# DAC.net
KiCad netlist of a schematic drawn in Altium Designer
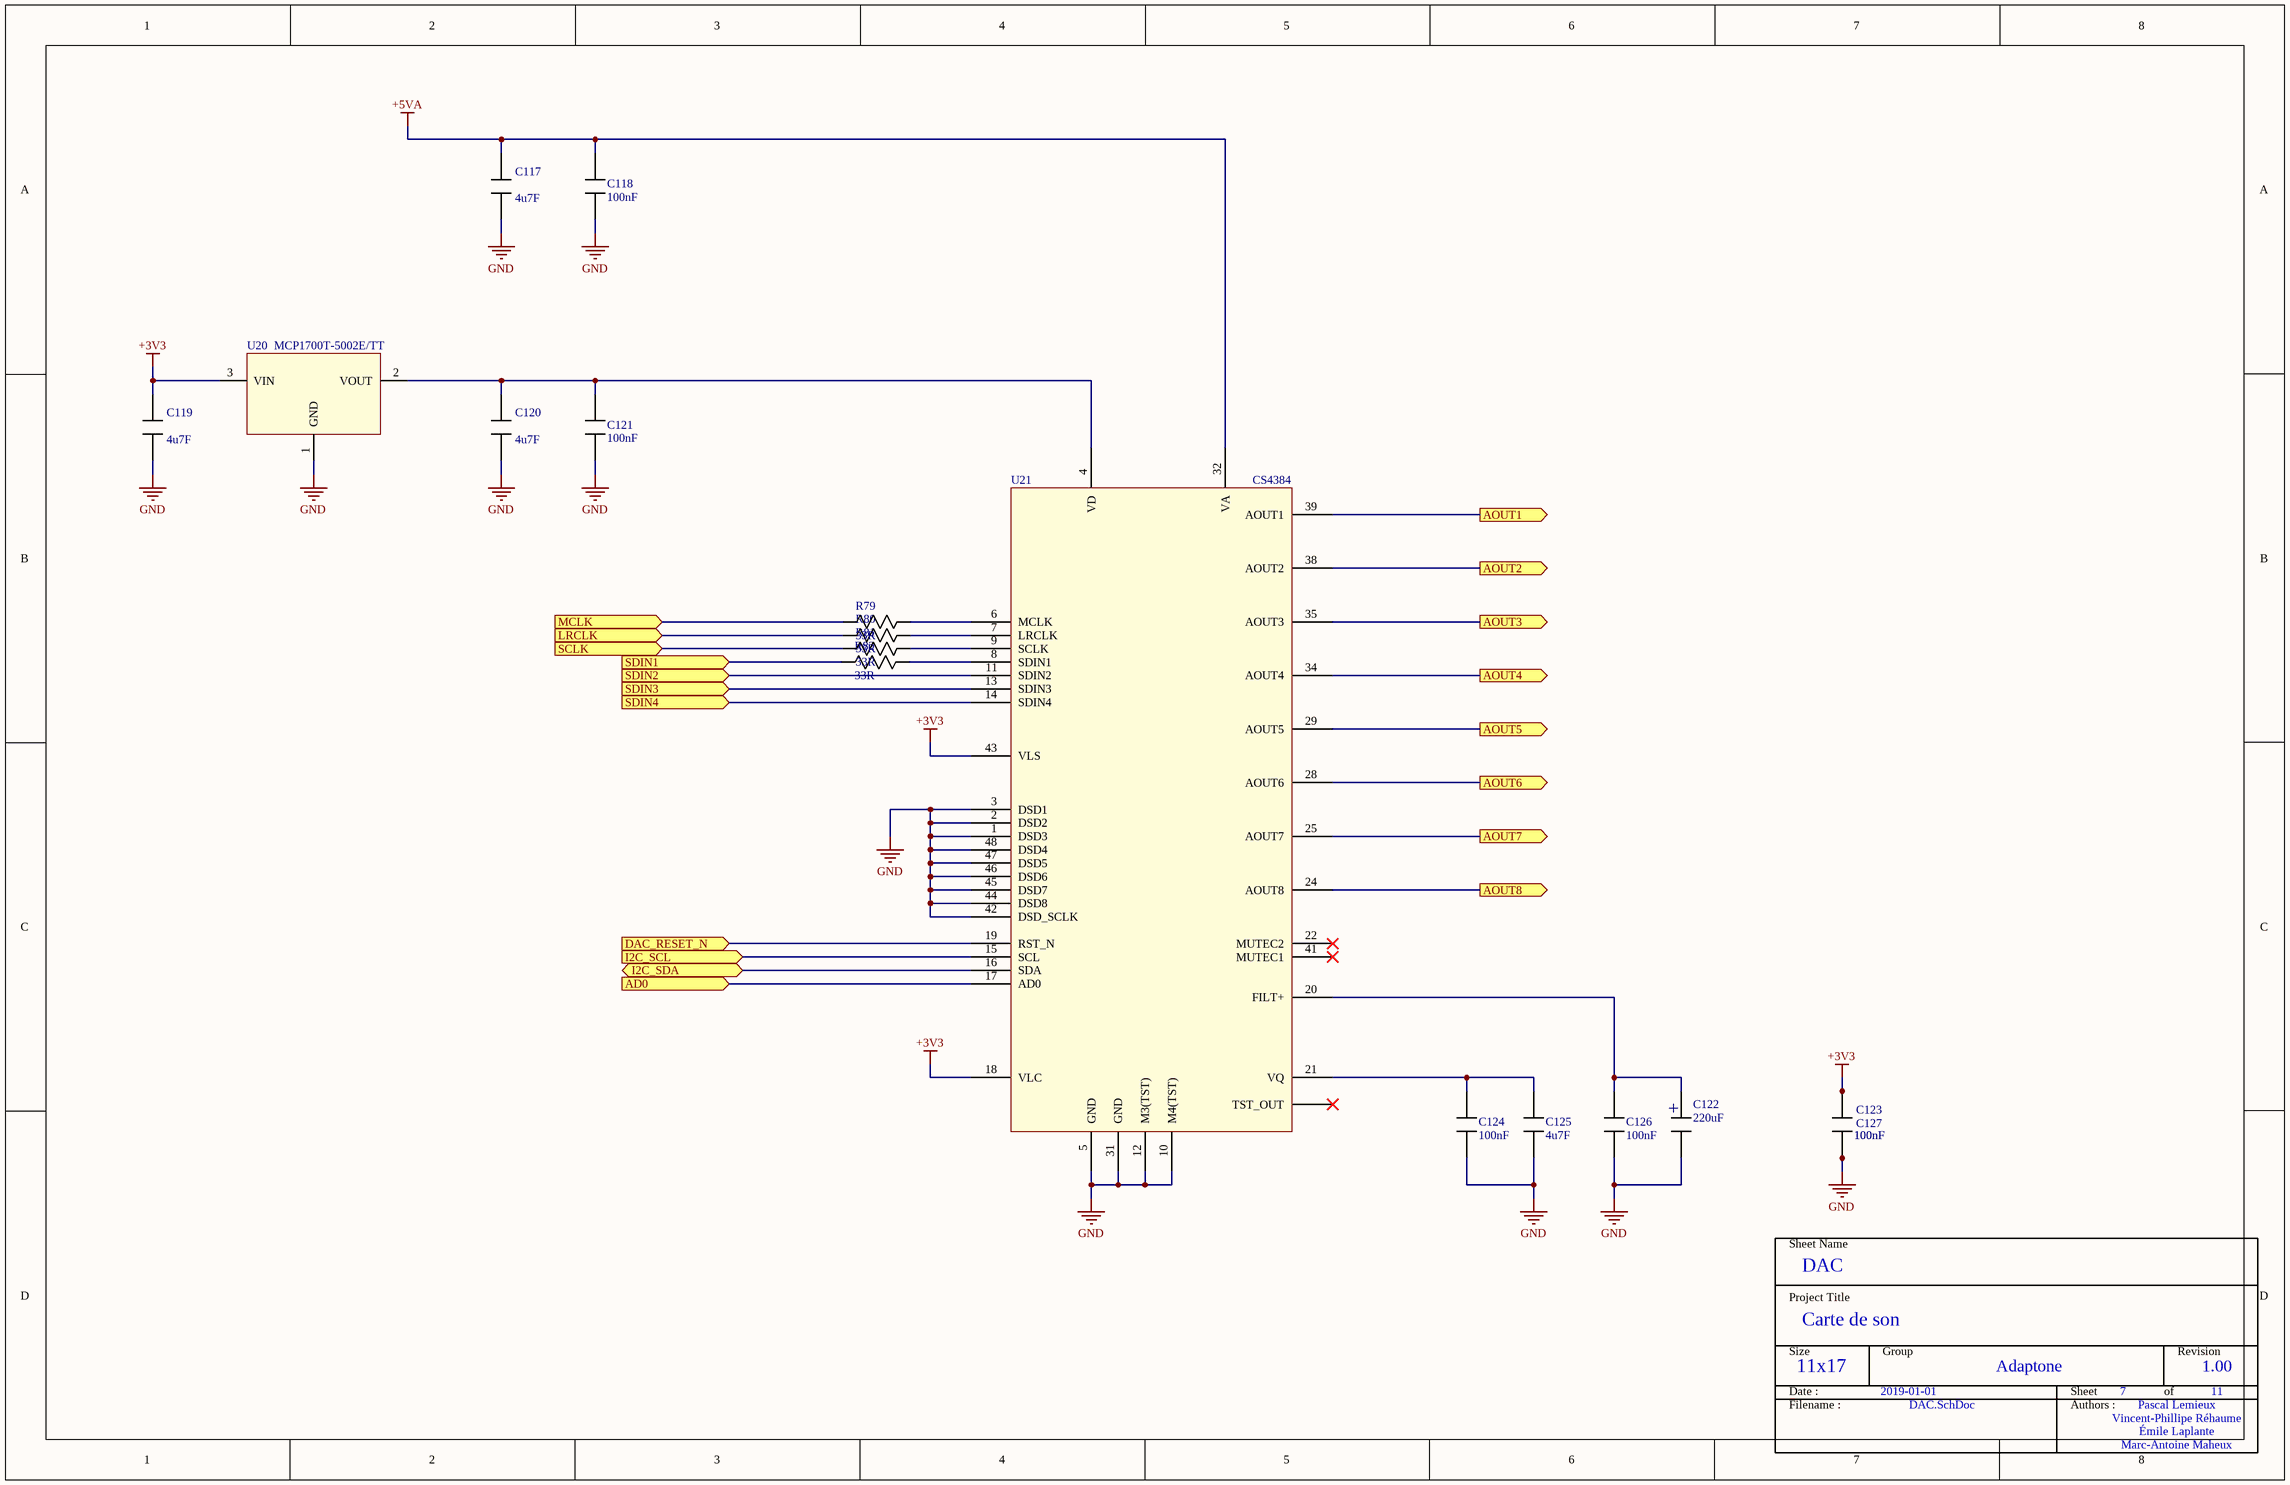
[diagram p0: DAC.SchDoc]

(export (version "E")
  (design (tool "Eeschema 10.0.6"))
  (components
    (comp (ref "C117")
      (value "4u7F")
      (footprint "0603")
      (description "Capacitor")
      (fields (field (name "MFG") "Samsung"))
      (libsource (lib "ADAPTONE_CARTE_DE_SON") (part "Capacitor"))
    )
    (comp (ref "C118")
      (value "100nF")
      (footprint "0603")
      (description "Capacitor")
      (fields (field (name "MFG") "Samsung"))
      (libsource (lib "ADAPTONE_CARTE_DE_SON") (part "Capacitor"))
    )
    (comp (ref "C119")
      (value "4u7F")
      (footprint "0603")
      (description "Capacitor")
      (fields (field (name "MFG") "Samsung"))
      (libsource (lib "ADAPTONE_CARTE_DE_SON") (part "Capacitor"))
    )
    (comp (ref "C120")
      (value "4u7F")
      (footprint "0603")
      (description "Capacitor")
      (fields (field (name "MFG") "Samsung"))
      (libsource (lib "ADAPTONE_CARTE_DE_SON") (part "Capacitor"))
    )
    (comp (ref "C121")
      (value "100nF")
      (footprint "0603")
      (description "Capacitor")
      (fields (field (name "MFG") "Samsung"))
      (libsource (lib "ADAPTONE_CARTE_DE_SON") (part "Capacitor"))
    )
    (comp (ref "C122")
      (value "220uF")
      (footprint "CAP_RAD_SMD_DIA315")
      (description "Capacitor")
      (fields (field (name "MFG") "Nichicon") (field (name "Comment") "Capacitor_Polarized_1"))
      (libsource (lib "ADAPTONE_CARTE_DE_SON") (part "Capacitor_Polarized_1"))
    )
    (comp (ref "C123")
      (value "100nF")
      (footprint "0603")
      (description "Capacitor")
      (fields (field (name "MFG") "Samsung"))
      (libsource (lib "ADAPTONE_CARTE_DE_SON") (part "Capacitor"))
    )
    (comp (ref "C124")
      (value "100nF")
      (footprint "0603")
      (description "Capacitor")
      (fields (field (name "MFG") "Samsung"))
      (libsource (lib "ADAPTONE_CARTE_DE_SON") (part "Capacitor"))
    )
    (comp (ref "C125")
      (value "4u7F")
      (footprint "0603")
      (description "Capacitor")
      (fields (field (name "MFG") "Samsung"))
      (libsource (lib "ADAPTONE_CARTE_DE_SON") (part "Capacitor"))
    )
    (comp (ref "C126")
      (value "100nF")
      (footprint "0603")
      (description "Capacitor")
      (fields (field (name "MFG") "Samsung"))
      (libsource (lib "ADAPTONE_CARTE_DE_SON") (part "Capacitor"))
    )
    (comp (ref "C127")
      (value "100nF")
      (footprint "0603")
      (description "Capacitor")
      (fields (field (name "MFG") "Samsung"))
      (libsource (lib "ADAPTONE_CARTE_DE_SON") (part "Capacitor"))
    )
    (comp (ref "R79")
      (value "33R")
      (footprint "0603")
      (description "Resistor")
      (fields (field (name "MFG") "Yageo"))
      (libsource (lib "ADAPTONE_CARTE_DE_SON") (part "Resistor"))
    )
    (comp (ref "R80")
      (value "33R")
      (footprint "0603")
      (description "Resistor")
      (fields (field (name "MFG") "Yageo"))
      (libsource (lib "ADAPTONE_CARTE_DE_SON") (part "Resistor"))
    )
    (comp (ref "R81")
      (value "33R")
      (footprint "0603")
      (description "Resistor")
      (fields (field (name "MFG") "Yageo"))
      (libsource (lib "ADAPTONE_CARTE_DE_SON") (part "Resistor"))
    )
    (comp (ref "R82")
      (value "33R")
      (footprint "0603")
      (description "Resistor")
      (fields (field (name "MFG") "Yageo"))
      (libsource (lib "ADAPTONE_CARTE_DE_SON") (part "Resistor"))
    )
    (comp (ref "U20")
      (value "MCP1700")
      (footprint "SOT23_132")
      (description "Linear voltage regulator")
      (fields (field (name "MFG") "Microchip") (field (name "MFG_PN") "MCP1700T-5002E/TT"))
      (libsource (lib "ADAPTONE_CARTE_DE_SON") (part "MCP1700"))
    )
    (comp (ref "U21")
      (value "CS4384")
      (footprint "LQFP_48L_CIRRUS")
      (description "DAC, 24-bit, 8 chan, 192kHz, PCM, TDM, DSD, LQFP48")
      (fields (field (name "MFG") "Cirrus"))
      (libsource (lib "ADAPTONE_CARTE_DE_SON") (part "CS4384"))
    )
  )
  (nets
    (net (code "1") (name "+3V3") (class "Default")
      (node (ref "C119") (pin "1") (pintype "passive"))
      (node (ref "C123") (pin "1") (pintype "passive"))
      (node (ref "C127") (pin "1") (pintype "passive"))
      (node (ref "U20") (pin "3") (pinfunction "VIN_3") (pintype "passive"))
      (node (ref "U21") (pin "18") (pinfunction "VLC_18") (pintype "passive"))
      (node (ref "U21") (pin "43") (pinfunction "VLS_43") (pintype "passive"))
    )
    (net (code "2") (name "+5VA") (class "Default")
      (node (ref "C117") (pin "1") (pintype "passive"))
      (node (ref "C118") (pin "1") (pintype "passive"))
      (node (ref "U21") (pin "32") (pinfunction "VA_32") (pintype "passive"))
    )
    (net (code "3") (name "/AD0") (class "Default")
      (node (ref "U21") (pin "17") (pinfunction "AD0_17") (pintype "passive"))
    )
    (net (code "4") (name "/AOUT1") (class "Default")
      (node (ref "U21") (pin "39") (pinfunction "AOUT1_39") (pintype "passive"))
    )
    (net (code "5") (name "/AOUT2") (class "Default")
      (node (ref "U21") (pin "38") (pinfunction "AOUT2_38") (pintype "passive"))
    )
    (net (code "6") (name "/AOUT3") (class "Default")
      (node (ref "U21") (pin "35") (pinfunction "AOUT3_35") (pintype "passive"))
    )
    (net (code "7") (name "/AOUT4") (class "Default")
      (node (ref "U21") (pin "34") (pinfunction "AOUT4_34") (pintype "passive"))
    )
    (net (code "8") (name "/AOUT5") (class "Default")
      (node (ref "U21") (pin "29") (pinfunction "AOUT5_29") (pintype "passive"))
    )
    (net (code "9") (name "/AOUT6") (class "Default")
      (node (ref "U21") (pin "28") (pinfunction "AOUT6_28") (pintype "passive"))
    )
    (net (code "10") (name "/AOUT7") (class "Default")
      (node (ref "U21") (pin "25") (pinfunction "AOUT7_25") (pintype "passive"))
    )
    (net (code "11") (name "/AOUT8") (class "Default")
      (node (ref "U21") (pin "24") (pinfunction "AOUT8_24") (pintype "passive"))
    )
    (net (code "12") (name "/DAC_RESET_N") (class "Default")
      (node (ref "U21") (pin "19") (pinfunction "RST_N_19") (pintype "passive"))
    )
    (net (code "13") (name "/I2C_SCL") (class "Default")
      (node (ref "U21") (pin "15") (pinfunction "SCL_15") (pintype "passive"))
    )
    (net (code "14") (name "/I2C_SDA") (class "Default")
      (node (ref "U21") (pin "16") (pinfunction "SDA_16") (pintype "passive"))
    )
    (net (code "15") (name "/LRCLK") (class "Default") (node (ref "R80") (pin "1") (pintype "passive")))
    (net (code "16") (name "/MCLK") (class "Default") (node (ref "R79") (pin "1") (pintype "passive")))
    (net (code "17") (name "/SCLK") (class "Default") (node (ref "R81") (pin "1") (pintype "passive")))
    (net (code "18") (name "/SDIN1") (class "Default") (node (ref "R82") (pin "1") (pintype "passive")))
    (net (code "19") (name "/SDIN2") (class "Default")
      (node (ref "U21") (pin "11") (pinfunction "SDIN2_11") (pintype "passive"))
    )
    (net (code "20") (name "/SDIN3") (class "Default")
      (node (ref "U21") (pin "13") (pinfunction "SDIN3_13") (pintype "passive"))
    )
    (net (code "21") (name "/SDIN4") (class "Default")
      (node (ref "U21") (pin "14") (pinfunction "SDIN4_14") (pintype "passive"))
    )
    (net (code "22") (name "GND") (class "Default")
      (node (ref "C117") (pin "2") (pintype "passive"))
      (node (ref "C118") (pin "2") (pintype "passive"))
      (node (ref "C119") (pin "2") (pintype "passive"))
      (node (ref "C120") (pin "2") (pintype "passive"))
      (node (ref "C121") (pin "2") (pintype "passive"))
      (node (ref "C122") (pin "-") (pintype "passive"))
      (node (ref "C123") (pin "2") (pintype "passive"))
      (node (ref "C124") (pin "2") (pintype "passive"))
      (node (ref "C125") (pin "2") (pintype "passive"))
      (node (ref "C126") (pin "2") (pintype "passive"))
      (node (ref "C127") (pin "2") (pintype "passive"))
      (node (ref "U20") (pin "1") (pinfunction "GND_1") (pintype "passive"))
      (node (ref "U21") (pin "1") (pinfunction "DSD3_1") (pintype "passive"))
      (node (ref "U21") (pin "10") (pinfunction "M4(TST)_10") (pintype "passive"))
      (node (ref "U21") (pin "12") (pinfunction "M3(TST)_12") (pintype "passive"))
      (node (ref "U21") (pin "2") (pinfunction "DSD2_2") (pintype "passive"))
      (node (ref "U21") (pin "3") (pinfunction "DSD1_3") (pintype "passive"))
      (node (ref "U21") (pin "31") (pinfunction "GND_31") (pintype "passive"))
      (node (ref "U21") (pin "42") (pinfunction "DSD_SCLK_42") (pintype "passive"))
      (node (ref "U21") (pin "44") (pinfunction "DSD8_44") (pintype "passive"))
      (node (ref "U21") (pin "45") (pinfunction "DSD7_45") (pintype "passive"))
      (node (ref "U21") (pin "46") (pinfunction "DSD6_46") (pintype "passive"))
      (node (ref "U21") (pin "47") (pinfunction "DSD5_47") (pintype "passive"))
      (node (ref "U21") (pin "48") (pinfunction "DSD4_48") (pintype "passive"))
      (node (ref "U21") (pin "5") (pinfunction "GND_5") (pintype "passive"))
    )
    (net (code "23") (name "Net-(U20-VOUT)") (class "Default")
      (node (ref "C120") (pin "1") (pintype "passive"))
      (node (ref "C121") (pin "1") (pintype "passive"))
      (node (ref "U20") (pin "2") (pinfunction "VOUT_2") (pintype "passive"))
      (node (ref "U21") (pin "4") (pinfunction "VD_4") (pintype "passive"))
    )
    (net (code "24") (name "Net-(U21-FILT+)") (class "Default")
      (node (ref "C122") (pin "+") (pintype "passive"))
      (node (ref "C126") (pin "1") (pintype "passive"))
      (node (ref "U21") (pin "20") (pinfunction "FILT+_20") (pintype "passive"))
    )
    (net (code "25") (name "Net-(U21-LRCLK)") (class "Default")
      (node (ref "R80") (pin "2") (pintype "passive"))
      (node (ref "U21") (pin "7") (pinfunction "LRCLK_7") (pintype "passive"))
    )
    (net (code "26") (name "Net-(U21-MCLK)") (class "Default")
      (node (ref "R79") (pin "2") (pintype "passive"))
      (node (ref "U21") (pin "6") (pinfunction "MCLK_6") (pintype "passive"))
    )
    (net (code "27") (name "Net-(U21-SCLK)") (class "Default")
      (node (ref "R81") (pin "2") (pintype "passive"))
      (node (ref "U21") (pin "9") (pinfunction "SCLK_9") (pintype "passive"))
    )
    (net (code "28") (name "Net-(U21-SDIN1)") (class "Default")
      (node (ref "R82") (pin "2") (pintype "passive"))
      (node (ref "U21") (pin "8") (pinfunction "SDIN1_8") (pintype "passive"))
    )
    (net (code "29") (name "Net-(U21-VQ)") (class "Default")
      (node (ref "C124") (pin "1") (pintype "passive"))
      (node (ref "C125") (pin "1") (pintype "passive"))
      (node (ref "U21") (pin "21") (pinfunction "VQ_21") (pintype "passive"))
    )
    (net (code "30") (name "unconnected-(U21-MUTEC1-Pad41)") (class "Default")
      (node (ref "U21") (pin "41") (pinfunction "MUTEC1_41") (pintype "passive+no_connect"))
    )
    (net (code "31") (name "unconnected-(U21-MUTEC2-Pad22)") (class "Default")
      (node (ref "U21") (pin "22") (pinfunction "MUTEC2_22") (pintype "passive+no_connect"))
    )
    (net (code "32") (name "unconnected-(U21-TST_OUT-Pad23)") (class "Default")
      (node (ref "U21") (pin "23") (pinfunction "TST_OUT_23") (pintype "passive"))
    )
    (net (code "33") (name "unconnected-(U21-TST_OUT-Pad26)") (class "Default")
      (node (ref "U21") (pin "26") (pinfunction "TST_OUT_26") (pintype "passive"))
    )
    (net (code "34") (name "unconnected-(U21-TST_OUT-Pad27)") (class "Default")
      (node (ref "U21") (pin "27") (pinfunction "TST_OUT_27") (pintype "passive"))
    )
    (net (code "35") (name "unconnected-(U21-TST_OUT-Pad30)") (class "Default")
      (node (ref "U21") (pin "30") (pinfunction "TST_OUT_30") (pintype "passive"))
    )
    (net (code "36") (name "unconnected-(U21-TST_OUT-Pad33)") (class "Default")
      (node (ref "U21") (pin "33") (pinfunction "TST_OUT_33") (pintype "passive"))
    )
    (net (code "37") (name "unconnected-(U21-TST_OUT-Pad36)") (class "Default")
      (node (ref "U21") (pin "36") (pinfunction "TST_OUT_36") (pintype "passive"))
    )
    (net (code "38") (name "unconnected-(U21-TST_OUT-Pad37)") (class "Default")
      (node (ref "U21") (pin "37") (pinfunction "TST_OUT_37") (pintype "passive"))
    )
    (net (code "39") (name "unconnected-(U21-TST_OUT-Pad40)") (class "Default")
      (node (ref "U21") (pin "40") (pinfunction "TST_OUT_40") (pintype "passive+no_connect"))
    )
  )
)
